# M3_SN755410.net
KiCad netlist of a schematic drawn in EAGLE
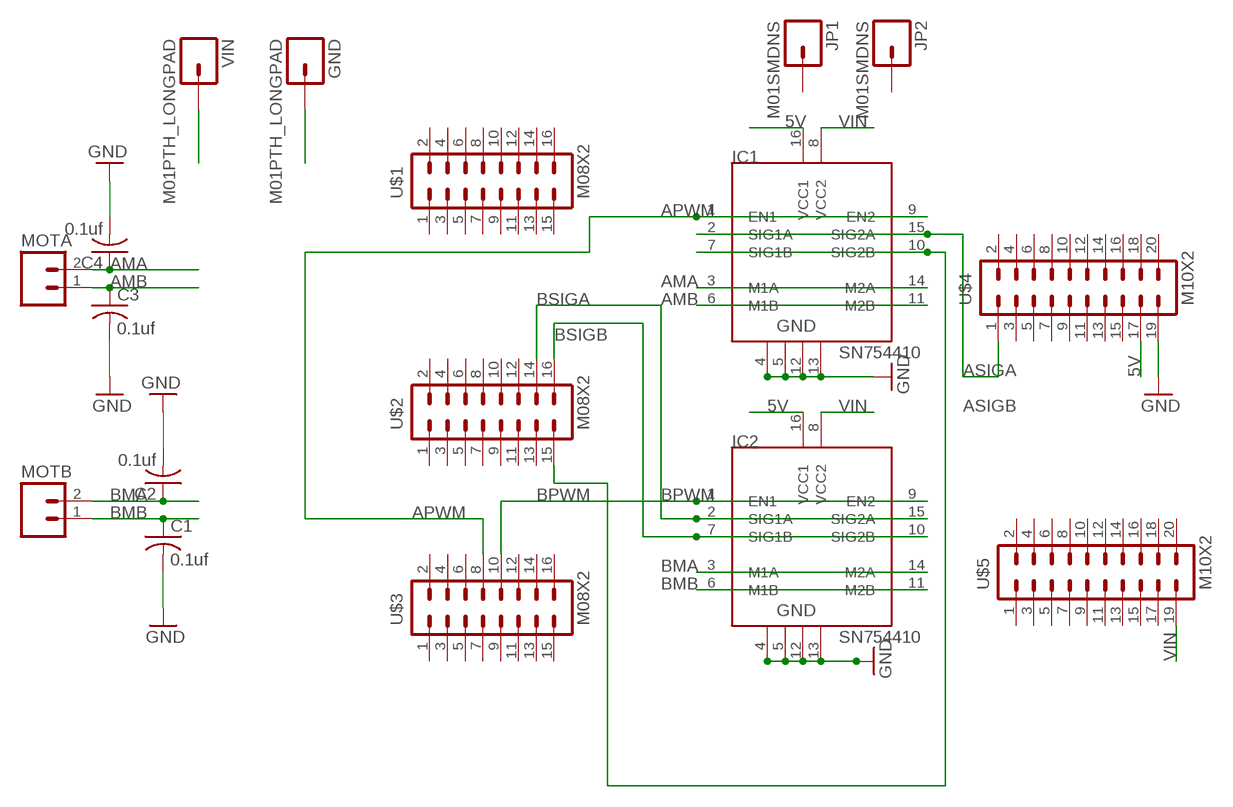
[diagram p0: schematic, sheet 1]

(export (version "E")
  (design (tool "Eeschema 10.0.6"))
  (components
    (comp (ref "C1")
      (value "0.1uf")
      (footprint "eagle-import:C0805")
      (libsource (lib "eagle-import") (part "C-USC0805"))
    )
    (comp (ref "C2")
      (value "0.1uf")
      (footprint "eagle-import:C0805")
      (libsource (lib "eagle-import") (part "C-USC0805"))
    )
    (comp (ref "C3")
      (value "0.1uf")
      (footprint "eagle-import:C0805")
      (libsource (lib "eagle-import") (part "C-USC0805"))
    )
    (comp (ref "C4")
      (value "0.1uf")
      (footprint "eagle-import:C0805")
      (libsource (lib "eagle-import") (part "C-USC0805"))
    )
    (comp (ref "GND")
      (value "M01PTH_LONGPAD")
      (footprint "eagle-import:1X01_LONGPAD")
      (libsource (lib "eagle-import") (part "M01PTH_LONGPAD"))
    )
    (comp (ref "IC1")
      (value "SN754410")
      (footprint "eagle-import:DIP16")
      (libsource (lib "eagle-import") (part "SN754410"))
    )
    (comp (ref "IC2")
      (value "SN754410")
      (footprint "eagle-import:DIP16")
      (libsource (lib "eagle-import") (part "SN754410"))
    )
    (comp (ref "JP1")
      (value "M01SMDNS")
      (footprint "eagle-import:1X01NS")
      (libsource (lib "eagle-import") (part "M01SMDNS"))
    )
    (comp (ref "JP2")
      (value "M01SMDNS")
      (footprint "eagle-import:1X01NS")
      (libsource (lib "eagle-import") (part "M01SMDNS"))
    )
    (comp (ref "MOTA")
      (value "M02PTH3")
      (footprint "eagle-import:1X02_LONGPADS")
      (libsource (lib "eagle-import") (part "M02PTH3"))
    )
    (comp (ref "MOTB")
      (value "M02PTH3")
      (footprint "eagle-import:1X02_LONGPADS")
      (libsource (lib "eagle-import") (part "M02PTH3"))
    )
    (comp (ref "U$1")
      (value "M08X2")
      (footprint "eagle-import:2X8")
      (libsource (lib "eagle-import") (part "M08X2"))
    )
    (comp (ref "U$2")
      (value "M08X2")
      (footprint "eagle-import:2X8")
      (libsource (lib "eagle-import") (part "M08X2"))
    )
    (comp (ref "U$3")
      (value "M08X2")
      (footprint "eagle-import:2X8")
      (libsource (lib "eagle-import") (part "M08X2"))
    )
    (comp (ref "U$4")
      (value "M10X2")
      (footprint "eagle-import:2X10")
      (libsource (lib "eagle-import") (part "M10X2"))
    )
    (comp (ref "U$5")
      (value "M10X2")
      (footprint "eagle-import:2X10")
      (libsource (lib "eagle-import") (part "M10X2"))
    )
    (comp (ref "VIN")
      (value "M01PTH_LONGPAD")
      (footprint "eagle-import:1X01_LONGPAD")
      (libsource (lib "eagle-import") (part "M01PTH_LONGPAD"))
    )
  )
  (nets
    (net (code "1") (name "/5V") (class "Default")
      (node (ref "IC1") (pin "16") (pinfunction "VCC1_16") (pintype "power_in"))
      (node (ref "IC2") (pin "16") (pinfunction "VCC1_16") (pintype "power_in"))
      (node (ref "U$4") (pin "17") (pinfunction "17_17") (pintype "passive"))
    )
    (net (code "2") (name "/AMA") (class "Default")
      (node (ref "C4") (pin "1") (pinfunction "1_1") (pintype "passive"))
      (node (ref "IC1") (pin "14") (pinfunction "M2A_14") (pintype "bidirectional"))
      (node (ref "IC1") (pin "3") (pinfunction "M1A_3") (pintype "bidirectional"))
      (node (ref "MOTA") (pin "2") (pinfunction "2_2") (pintype "passive"))
    )
    (net (code "3") (name "/AMB") (class "Default")
      (node (ref "C3") (pin "1") (pinfunction "1_1") (pintype "passive"))
      (node (ref "IC1") (pin "11") (pinfunction "M2B_11") (pintype "bidirectional"))
      (node (ref "IC1") (pin "6") (pinfunction "M1B_6") (pintype "bidirectional"))
      (node (ref "MOTA") (pin "1") (pinfunction "1_1") (pintype "passive"))
    )
    (net (code "4") (name "/APWM") (class "Default")
      (node (ref "IC1") (pin "1") (pinfunction "EN1_1") (pintype "bidirectional"))
      (node (ref "IC1") (pin "9") (pinfunction "EN2_9") (pintype "bidirectional"))
      (node (ref "U$3") (pin "8") (pinfunction "8_8") (pintype "passive"))
    )
    (net (code "5") (name "/ASIGA") (class "Default")
      (node (ref "IC1") (pin "15") (pinfunction "SIG2A_15") (pintype "bidirectional"))
      (node (ref "IC1") (pin "2") (pinfunction "SIG1A_2") (pintype "bidirectional"))
      (node (ref "U$4") (pin "1") (pinfunction "1_1") (pintype "passive"))
    )
    (net (code "6") (name "/ASIGB") (class "Default")
      (node (ref "IC1") (pin "10") (pinfunction "SIG2B_10") (pintype "bidirectional"))
      (node (ref "IC1") (pin "7") (pinfunction "SIG1B_7") (pintype "bidirectional"))
      (node (ref "U$2") (pin "15") (pinfunction "15_15") (pintype "passive"))
    )
    (net (code "7") (name "/BMA") (class "Default")
      (node (ref "C2") (pin "1") (pinfunction "1_1") (pintype "passive"))
      (node (ref "IC2") (pin "14") (pinfunction "M2A_14") (pintype "bidirectional"))
      (node (ref "IC2") (pin "3") (pinfunction "M1A_3") (pintype "bidirectional"))
      (node (ref "MOTB") (pin "2") (pinfunction "2_2") (pintype "passive"))
    )
    (net (code "8") (name "/BMB") (class "Default")
      (node (ref "C1") (pin "1") (pinfunction "1_1") (pintype "passive"))
      (node (ref "IC2") (pin "11") (pinfunction "M2B_11") (pintype "bidirectional"))
      (node (ref "IC2") (pin "6") (pinfunction "M1B_6") (pintype "bidirectional"))
      (node (ref "MOTB") (pin "1") (pinfunction "1_1") (pintype "passive"))
    )
    (net (code "9") (name "/BPWM") (class "Default")
      (node (ref "IC2") (pin "1") (pinfunction "EN1_1") (pintype "bidirectional"))
      (node (ref "IC2") (pin "9") (pinfunction "EN2_9") (pintype "bidirectional"))
      (node (ref "U$3") (pin "10") (pinfunction "10_10") (pintype "passive"))
    )
    (net (code "10") (name "/BSIGA") (class "Default")
      (node (ref "IC2") (pin "15") (pinfunction "SIG2A_15") (pintype "bidirectional"))
      (node (ref "IC2") (pin "2") (pinfunction "SIG1A_2") (pintype "bidirectional"))
      (node (ref "U$2") (pin "14") (pinfunction "14_14") (pintype "passive"))
    )
    (net (code "11") (name "/BSIGB") (class "Default")
      (node (ref "IC2") (pin "10") (pinfunction "SIG2B_10") (pintype "bidirectional"))
      (node (ref "IC2") (pin "7") (pinfunction "SIG1B_7") (pintype "bidirectional"))
      (node (ref "U$2") (pin "16") (pinfunction "16_16") (pintype "passive"))
    )
    (net (code "12") (name "/VIN") (class "Default")
      (node (ref "IC1") (pin "8") (pinfunction "VCC2_8") (pintype "power_in"))
      (node (ref "IC2") (pin "8") (pinfunction "VCC2_8") (pintype "power_in"))
      (node (ref "U$5") (pin "19") (pinfunction "19_19") (pintype "passive"))
      (node (ref "VIN") (pin "1") (pinfunction "1_1") (pintype "passive"))
    )
    (net (code "13") (name "GND") (class "Default")
      (node (ref "C1") (pin "2") (pinfunction "2_2") (pintype "passive"))
      (node (ref "C2") (pin "2") (pinfunction "2_2") (pintype "passive"))
      (node (ref "C3") (pin "2") (pinfunction "2_2") (pintype "passive"))
      (node (ref "C4") (pin "2") (pinfunction "2_2") (pintype "passive"))
      (node (ref "GND") (pin "1") (pinfunction "1_1") (pintype "passive"))
      (node (ref "IC1") (pin "12") (pinfunction "P12_12") (pintype "power_in"))
      (node (ref "IC1") (pin "13") (pinfunction "P13_13") (pintype "power_in"))
      (node (ref "IC1") (pin "4") (pinfunction "P4_4") (pintype "power_in"))
      (node (ref "IC1") (pin "5") (pinfunction "P5_5") (pintype "power_in"))
      (node (ref "IC2") (pin "12") (pinfunction "P12_12") (pintype "power_in"))
      (node (ref "IC2") (pin "13") (pinfunction "P13_13") (pintype "power_in"))
      (node (ref "IC2") (pin "4") (pinfunction "P4_4") (pintype "power_in"))
      (node (ref "IC2") (pin "5") (pinfunction "P5_5") (pintype "power_in"))
      (node (ref "U$4") (pin "19") (pinfunction "19_19") (pintype "passive"))
    )
    (net (code "14") (name "unconnected-(JP1-Pad1)") (class "Default")
      (node (ref "JP1") (pin "1") (pinfunction "1_1") (pintype "passive"))
    )
    (net (code "15") (name "unconnected-(JP2-Pad1)") (class "Default")
      (node (ref "JP2") (pin "1") (pinfunction "1_1") (pintype "passive"))
    )
    (net (code "16") (name "unconnected-(U$1-Pad1)") (class "Default")
      (node (ref "U$1") (pin "1") (pinfunction "1_1") (pintype "passive"))
    )
    (net (code "17") (name "unconnected-(U$1-Pad2)") (class "Default")
      (node (ref "U$1") (pin "2") (pinfunction "2_2") (pintype "passive"))
    )
    (net (code "18") (name "unconnected-(U$1-Pad3)") (class "Default")
      (node (ref "U$1") (pin "3") (pinfunction "3_3") (pintype "passive"))
    )
    (net (code "19") (name "unconnected-(U$1-Pad4)") (class "Default")
      (node (ref "U$1") (pin "4") (pinfunction "4_4") (pintype "passive"))
    )
    (net (code "20") (name "unconnected-(U$1-Pad5)") (class "Default")
      (node (ref "U$1") (pin "5") (pinfunction "5_5") (pintype "passive"))
    )
    (net (code "21") (name "unconnected-(U$1-Pad6)") (class "Default")
      (node (ref "U$1") (pin "6") (pinfunction "6_6") (pintype "passive"))
    )
    (net (code "22") (name "unconnected-(U$1-Pad7)") (class "Default")
      (node (ref "U$1") (pin "7") (pinfunction "7_7") (pintype "passive"))
    )
    (net (code "23") (name "unconnected-(U$1-Pad8)") (class "Default")
      (node (ref "U$1") (pin "8") (pinfunction "8_8") (pintype "passive"))
    )
    (net (code "24") (name "unconnected-(U$1-Pad9)") (class "Default")
      (node (ref "U$1") (pin "9") (pinfunction "9_9") (pintype "passive"))
    )
    (net (code "25") (name "unconnected-(U$1-Pad10)") (class "Default")
      (node (ref "U$1") (pin "10") (pinfunction "10_10") (pintype "passive"))
    )
    (net (code "26") (name "unconnected-(U$1-Pad11)") (class "Default")
      (node (ref "U$1") (pin "11") (pinfunction "11_11") (pintype "passive"))
    )
    (net (code "27") (name "unconnected-(U$1-Pad12)") (class "Default")
      (node (ref "U$1") (pin "12") (pinfunction "12_12") (pintype "passive"))
    )
    (net (code "28") (name "unconnected-(U$1-Pad13)") (class "Default")
      (node (ref "U$1") (pin "13") (pinfunction "13_13") (pintype "passive"))
    )
    (net (code "29") (name "unconnected-(U$1-Pad14)") (class "Default")
      (node (ref "U$1") (pin "14") (pinfunction "14_14") (pintype "passive"))
    )
    (net (code "30") (name "unconnected-(U$1-Pad15)") (class "Default")
      (node (ref "U$1") (pin "15") (pinfunction "15_15") (pintype "passive"))
    )
    (net (code "31") (name "unconnected-(U$1-Pad16)") (class "Default")
      (node (ref "U$1") (pin "16") (pinfunction "16_16") (pintype "passive"))
    )
    (net (code "32") (name "unconnected-(U$2-Pad1)") (class "Default")
      (node (ref "U$2") (pin "1") (pinfunction "1_1") (pintype "passive"))
    )
    (net (code "33") (name "unconnected-(U$2-Pad2)") (class "Default")
      (node (ref "U$2") (pin "2") (pinfunction "2_2") (pintype "passive"))
    )
    (net (code "34") (name "unconnected-(U$2-Pad3)") (class "Default")
      (node (ref "U$2") (pin "3") (pinfunction "3_3") (pintype "passive"))
    )
    (net (code "35") (name "unconnected-(U$2-Pad4)") (class "Default")
      (node (ref "U$2") (pin "4") (pinfunction "4_4") (pintype "passive"))
    )
    (net (code "36") (name "unconnected-(U$2-Pad5)") (class "Default")
      (node (ref "U$2") (pin "5") (pinfunction "5_5") (pintype "passive"))
    )
    (net (code "37") (name "unconnected-(U$2-Pad6)") (class "Default")
      (node (ref "U$2") (pin "6") (pinfunction "6_6") (pintype "passive"))
    )
    (net (code "38") (name "unconnected-(U$2-Pad7)") (class "Default")
      (node (ref "U$2") (pin "7") (pinfunction "7_7") (pintype "passive"))
    )
    (net (code "39") (name "unconnected-(U$2-Pad8)") (class "Default")
      (node (ref "U$2") (pin "8") (pinfunction "8_8") (pintype "passive"))
    )
    (net (code "40") (name "unconnected-(U$2-Pad9)") (class "Default")
      (node (ref "U$2") (pin "9") (pinfunction "9_9") (pintype "passive"))
    )
    (net (code "41") (name "unconnected-(U$2-Pad10)") (class "Default")
      (node (ref "U$2") (pin "10") (pinfunction "10_10") (pintype "passive"))
    )
    (net (code "42") (name "unconnected-(U$2-Pad11)") (class "Default")
      (node (ref "U$2") (pin "11") (pinfunction "11_11") (pintype "passive"))
    )
    (net (code "43") (name "unconnected-(U$2-Pad12)") (class "Default")
      (node (ref "U$2") (pin "12") (pinfunction "12_12") (pintype "passive"))
    )
    (net (code "44") (name "unconnected-(U$2-Pad13)") (class "Default")
      (node (ref "U$2") (pin "13") (pinfunction "13_13") (pintype "passive"))
    )
    (net (code "45") (name "unconnected-(U$3-Pad1)") (class "Default")
      (node (ref "U$3") (pin "1") (pinfunction "1_1") (pintype "passive"))
    )
    (net (code "46") (name "unconnected-(U$3-Pad2)") (class "Default")
      (node (ref "U$3") (pin "2") (pinfunction "2_2") (pintype "passive"))
    )
    (net (code "47") (name "unconnected-(U$3-Pad3)") (class "Default")
      (node (ref "U$3") (pin "3") (pinfunction "3_3") (pintype "passive"))
    )
    (net (code "48") (name "unconnected-(U$3-Pad4)") (class "Default")
      (node (ref "U$3") (pin "4") (pinfunction "4_4") (pintype "passive"))
    )
    (net (code "49") (name "unconnected-(U$3-Pad5)") (class "Default")
      (node (ref "U$3") (pin "5") (pinfunction "5_5") (pintype "passive"))
    )
    (net (code "50") (name "unconnected-(U$3-Pad6)") (class "Default")
      (node (ref "U$3") (pin "6") (pinfunction "6_6") (pintype "passive"))
    )
    (net (code "51") (name "unconnected-(U$3-Pad7)") (class "Default")
      (node (ref "U$3") (pin "7") (pinfunction "7_7") (pintype "passive"))
    )
    (net (code "52") (name "unconnected-(U$3-Pad9)") (class "Default")
      (node (ref "U$3") (pin "9") (pinfunction "9_9") (pintype "passive"))
    )
    (net (code "53") (name "unconnected-(U$3-Pad11)") (class "Default")
      (node (ref "U$3") (pin "11") (pinfunction "11_11") (pintype "passive"))
    )
    (net (code "54") (name "unconnected-(U$3-Pad12)") (class "Default")
      (node (ref "U$3") (pin "12") (pinfunction "12_12") (pintype "passive"))
    )
    (net (code "55") (name "unconnected-(U$3-Pad13)") (class "Default")
      (node (ref "U$3") (pin "13") (pinfunction "13_13") (pintype "passive"))
    )
    (net (code "56") (name "unconnected-(U$3-Pad14)") (class "Default")
      (node (ref "U$3") (pin "14") (pinfunction "14_14") (pintype "passive"))
    )
    (net (code "57") (name "unconnected-(U$3-Pad15)") (class "Default")
      (node (ref "U$3") (pin "15") (pinfunction "15_15") (pintype "passive"))
    )
    (net (code "58") (name "unconnected-(U$3-Pad16)") (class "Default")
      (node (ref "U$3") (pin "16") (pinfunction "16_16") (pintype "passive"))
    )
    (net (code "59") (name "unconnected-(U$4-Pad2)") (class "Default")
      (node (ref "U$4") (pin "2") (pinfunction "2_2") (pintype "passive"))
    )
    (net (code "60") (name "unconnected-(U$4-Pad3)") (class "Default")
      (node (ref "U$4") (pin "3") (pinfunction "3_3") (pintype "passive"))
    )
    (net (code "61") (name "unconnected-(U$4-Pad4)") (class "Default")
      (node (ref "U$4") (pin "4") (pinfunction "4_4") (pintype "passive"))
    )
    (net (code "62") (name "unconnected-(U$4-Pad5)") (class "Default")
      (node (ref "U$4") (pin "5") (pinfunction "5_5") (pintype "passive"))
    )
    (net (code "63") (name "unconnected-(U$4-Pad6)") (class "Default")
      (node (ref "U$4") (pin "6") (pinfunction "6_6") (pintype "passive"))
    )
    (net (code "64") (name "unconnected-(U$4-Pad7)") (class "Default")
      (node (ref "U$4") (pin "7") (pinfunction "7_7") (pintype "passive"))
    )
    (net (code "65") (name "unconnected-(U$4-Pad8)") (class "Default")
      (node (ref "U$4") (pin "8") (pinfunction "8_8") (pintype "passive"))
    )
    (net (code "66") (name "unconnected-(U$4-Pad9)") (class "Default")
      (node (ref "U$4") (pin "9") (pinfunction "9_9") (pintype "passive"))
    )
    (net (code "67") (name "unconnected-(U$4-Pad10)") (class "Default")
      (node (ref "U$4") (pin "10") (pinfunction "10_10") (pintype "passive"))
    )
    (net (code "68") (name "unconnected-(U$4-Pad11)") (class "Default")
      (node (ref "U$4") (pin "11") (pinfunction "11_11") (pintype "passive"))
    )
    (net (code "69") (name "unconnected-(U$4-Pad12)") (class "Default")
      (node (ref "U$4") (pin "12") (pinfunction "12_12") (pintype "passive"))
    )
    (net (code "70") (name "unconnected-(U$4-Pad13)") (class "Default")
      (node (ref "U$4") (pin "13") (pinfunction "13_13") (pintype "passive"))
    )
    (net (code "71") (name "unconnected-(U$4-Pad14)") (class "Default")
      (node (ref "U$4") (pin "14") (pinfunction "14_14") (pintype "passive"))
    )
    (net (code "72") (name "unconnected-(U$4-Pad15)") (class "Default")
      (node (ref "U$4") (pin "15") (pinfunction "15_15") (pintype "passive"))
    )
    (net (code "73") (name "unconnected-(U$4-Pad16)") (class "Default")
      (node (ref "U$4") (pin "16") (pinfunction "16_16") (pintype "passive"))
    )
    (net (code "74") (name "unconnected-(U$4-Pad18)") (class "Default")
      (node (ref "U$4") (pin "18") (pinfunction "18_18") (pintype "passive"))
    )
    (net (code "75") (name "unconnected-(U$4-Pad20)") (class "Default")
      (node (ref "U$4") (pin "20") (pinfunction "20_20") (pintype "passive"))
    )
    (net (code "76") (name "unconnected-(U$5-Pad1)") (class "Default")
      (node (ref "U$5") (pin "1") (pinfunction "1_1") (pintype "passive"))
    )
    (net (code "77") (name "unconnected-(U$5-Pad2)") (class "Default")
      (node (ref "U$5") (pin "2") (pinfunction "2_2") (pintype "passive"))
    )
    (net (code "78") (name "unconnected-(U$5-Pad3)") (class "Default")
      (node (ref "U$5") (pin "3") (pinfunction "3_3") (pintype "passive"))
    )
    (net (code "79") (name "unconnected-(U$5-Pad4)") (class "Default")
      (node (ref "U$5") (pin "4") (pinfunction "4_4") (pintype "passive"))
    )
    (net (code "80") (name "unconnected-(U$5-Pad5)") (class "Default")
      (node (ref "U$5") (pin "5") (pinfunction "5_5") (pintype "passive"))
    )
    (net (code "81") (name "unconnected-(U$5-Pad6)") (class "Default")
      (node (ref "U$5") (pin "6") (pinfunction "6_6") (pintype "passive"))
    )
    (net (code "82") (name "unconnected-(U$5-Pad7)") (class "Default")
      (node (ref "U$5") (pin "7") (pinfunction "7_7") (pintype "passive"))
    )
    (net (code "83") (name "unconnected-(U$5-Pad8)") (class "Default")
      (node (ref "U$5") (pin "8") (pinfunction "8_8") (pintype "passive"))
    )
    (net (code "84") (name "unconnected-(U$5-Pad9)") (class "Default")
      (node (ref "U$5") (pin "9") (pinfunction "9_9") (pintype "passive"))
    )
    (net (code "85") (name "unconnected-(U$5-Pad10)") (class "Default")
      (node (ref "U$5") (pin "10") (pinfunction "10_10") (pintype "passive"))
    )
    (net (code "86") (name "unconnected-(U$5-Pad11)") (class "Default")
      (node (ref "U$5") (pin "11") (pinfunction "11_11") (pintype "passive"))
    )
    (net (code "87") (name "unconnected-(U$5-Pad12)") (class "Default")
      (node (ref "U$5") (pin "12") (pinfunction "12_12") (pintype "passive"))
    )
    (net (code "88") (name "unconnected-(U$5-Pad13)") (class "Default")
      (node (ref "U$5") (pin "13") (pinfunction "13_13") (pintype "passive"))
    )
    (net (code "89") (name "unconnected-(U$5-Pad14)") (class "Default")
      (node (ref "U$5") (pin "14") (pinfunction "14_14") (pintype "passive"))
    )
    (net (code "90") (name "unconnected-(U$5-Pad15)") (class "Default")
      (node (ref "U$5") (pin "15") (pinfunction "15_15") (pintype "passive"))
    )
    (net (code "91") (name "unconnected-(U$5-Pad16)") (class "Default")
      (node (ref "U$5") (pin "16") (pinfunction "16_16") (pintype "passive"))
    )
    (net (code "92") (name "unconnected-(U$5-Pad17)") (class "Default")
      (node (ref "U$5") (pin "17") (pinfunction "17_17") (pintype "passive"))
    )
    (net (code "93") (name "unconnected-(U$5-Pad18)") (class "Default")
      (node (ref "U$5") (pin "18") (pinfunction "18_18") (pintype "passive"))
    )
    (net (code "94") (name "unconnected-(U$5-Pad20)") (class "Default")
      (node (ref "U$5") (pin "20") (pinfunction "20_20") (pintype "passive"))
    )
  )
)
